# psas_c3.net
KiCad netlist of a schematic drawn in EAGLE
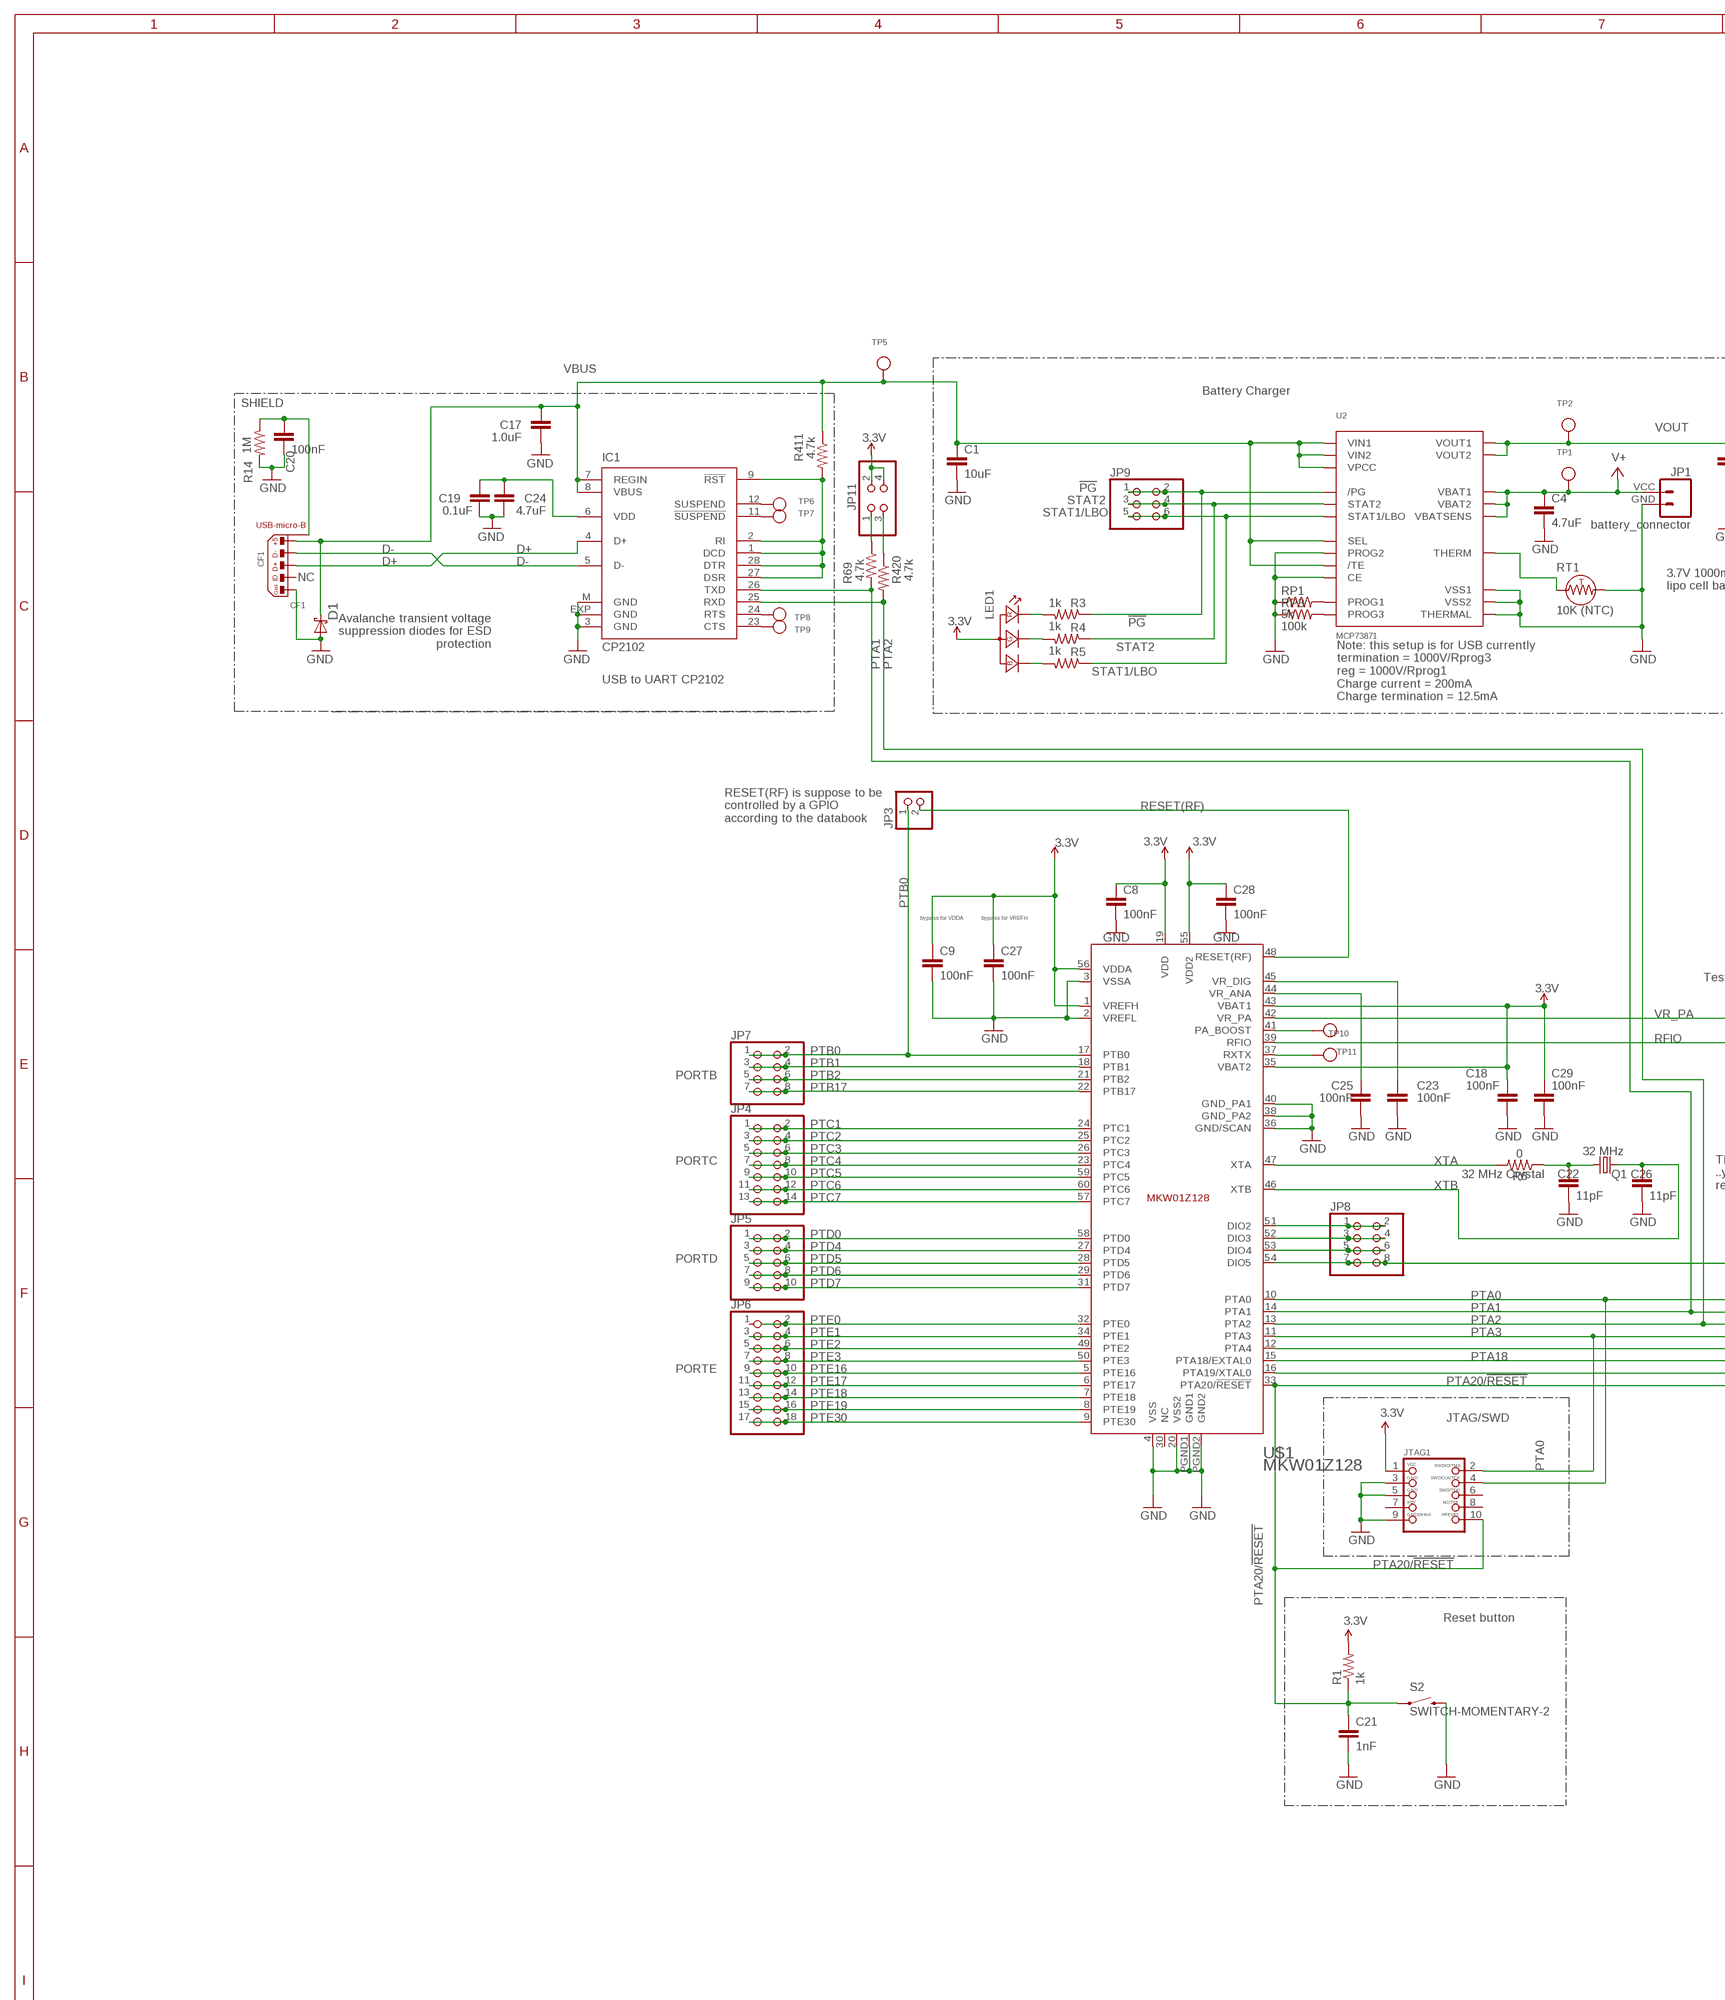
[diagram p0: schematic, sheet 1, part 1 of 2]
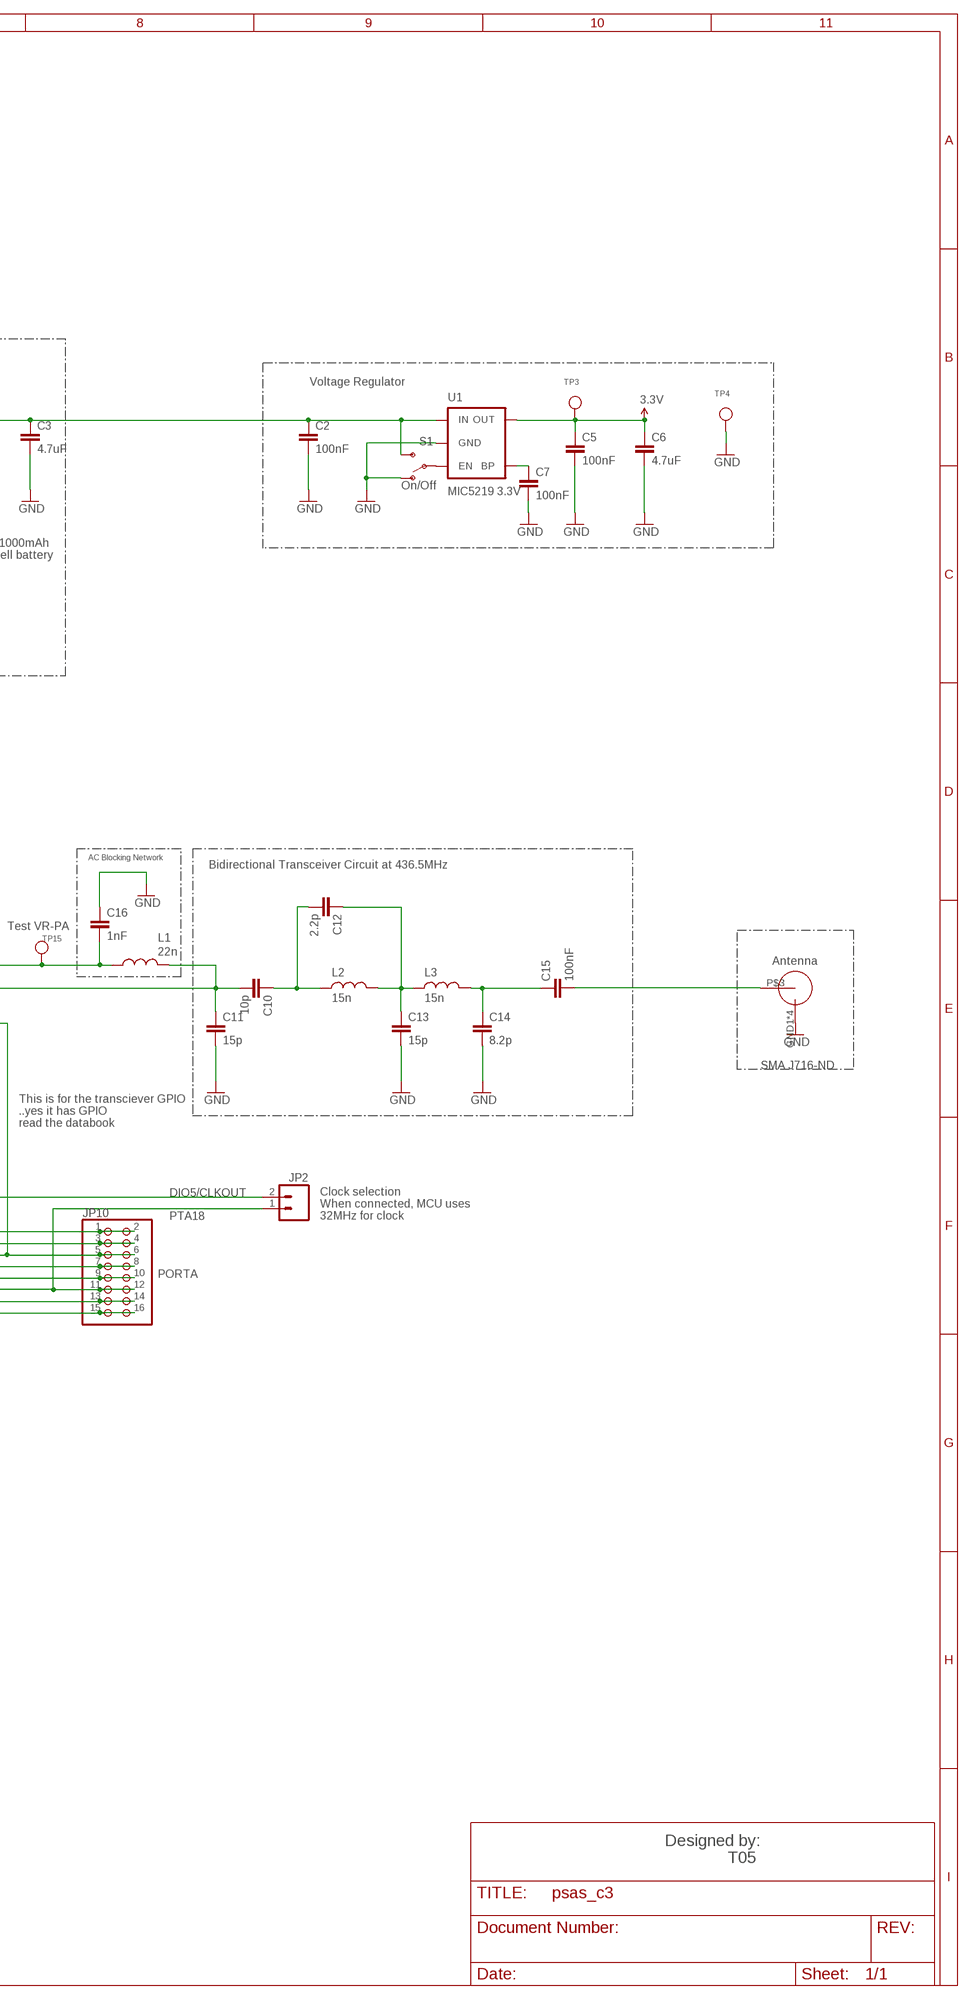
[diagram p1: schematic, sheet 1, part 2 of 2]

(export (version "E")
  (design (tool "Eeschema 10.0.6"))
  (components
    (comp (ref "C1")
      (value "10uF")
      (footprint "eagle-import:.0603-B-NOSILK")
      (libsource (lib "eagle-import") (part "rcl_custom_C-EU0603-B-NOSILK"))
    )
    (comp (ref "C2")
      (value "100nF")
      (footprint "eagle-import:.0603-B-NOSILK")
      (libsource (lib "eagle-import") (part "rcl_custom_C-EU0603-B-NOSILK"))
    )
    (comp (ref "C3")
      (value "4.7uF")
      (footprint "eagle-import:.0603-B-NOSILK")
      (libsource (lib "eagle-import") (part "rcl_custom_C-EU0603-B-NOSILK"))
    )
    (comp (ref "C4")
      (value "4.7uF")
      (footprint "eagle-import:.0603-B-NOSILK")
      (libsource (lib "eagle-import") (part "rcl_custom_C-EU0603-B-NOSILK"))
    )
    (comp (ref "C5")
      (value "100nF")
      (footprint "eagle-import:.0603-B-NOSILK")
      (libsource (lib "eagle-import") (part "rcl_custom_C-EU0603-B-NOSILK"))
    )
    (comp (ref "C6")
      (value "4.7uF")
      (footprint "eagle-import:.0603-B-NOSILK")
      (libsource (lib "eagle-import") (part "rcl_custom_C-EU0603-B-NOSILK"))
    )
    (comp (ref "C7")
      (value "100nF")
      (footprint "eagle-import:.0603-B-NOSILK")
      (libsource (lib "eagle-import") (part "rcl_custom_C-EU0603-B-NOSILK"))
    )
    (comp (ref "C8")
      (value "100nF")
      (footprint "eagle-import:.0603-B-NOSILK")
      (fields
        (field (name "MFG") "Murata Electronics North America")
        (field (name "MPN") "GRM188R71C104KA01D")
      )
      (libsource (lib "eagle-import") (part "C-EU0603-B-NOSILK"))
    )
    (comp (ref "C9")
      (value "100nF")
      (footprint "eagle-import:.0603-B-NOSILK")
      (fields
        (field (name "MFG") "Murata Electronics North America")
        (field (name "MPN") "GRM188R71C104KA01D")
      )
      (libsource (lib "eagle-import") (part "C-EU0603-B-NOSILK"))
    )
    (comp (ref "C10")
      (value "10p")
      (footprint "eagle-import:.0603-B-NOSILK")
      (libsource (lib "eagle-import") (part "rcl_custom_C-EU0603-B-NOSILK"))
    )
    (comp (ref "C11")
      (value "15p")
      (footprint "eagle-import:.0603-B-NOSILK")
      (libsource (lib "eagle-import") (part "rcl_custom_C-EU0603-B-NOSILK"))
    )
    (comp (ref "C12")
      (value "2.2p")
      (footprint "eagle-import:.0603-B-NOSILK")
      (libsource (lib "eagle-import") (part "rcl_custom_C-EU0603-B-NOSILK"))
    )
    (comp (ref "C13")
      (value "15p")
      (footprint "eagle-import:.0603-B-NOSILK")
      (libsource (lib "eagle-import") (part "rcl_custom_C-EU0603-B-NOSILK"))
    )
    (comp (ref "C14")
      (value "8.2p")
      (footprint "eagle-import:.0603-B-NOSILK")
      (libsource (lib "eagle-import") (part "rcl_custom_C-EU0603-B-NOSILK"))
    )
    (comp (ref "C15")
      (value "100nF")
      (footprint "eagle-import:.0603-B-NOSILK")
      (libsource (lib "eagle-import") (part "rcl_custom_C-EU0603-B-NOSILK"))
    )
    (comp (ref "C16")
      (value "1nF")
      (footprint "eagle-import:.0603-B-NOSILK")
      (libsource (lib "eagle-import") (part "rcl_custom_C-EU0603-B-NOSILK"))
    )
    (comp (ref "C17")
      (value "1.0uF")
      (footprint "eagle-import:.0603-B-NOSILK")
      (libsource (lib "eagle-import") (part "rcl_custom_C-EU0603-B-NOSILK"))
    )
    (comp (ref "C18")
      (value "100nF")
      (footprint "eagle-import:.0603-B-NOSILK")
      (fields
        (field (name "MFG") "Murata Electronics North America")
        (field (name "MPN") "GRM188R71C104KA01D")
      )
      (libsource (lib "eagle-import") (part "C-EU0603-B-NOSILK"))
    )
    (comp (ref "C19")
      (value "0.1uF")
      (footprint "eagle-import:.0603-B-NOSILK")
      (libsource (lib "eagle-import") (part "rcl_custom_C-EU0603-B-NOSILK"))
    )
    (comp (ref "C20")
      (value "100nF")
      (footprint "eagle-import:.0603-B-NOSILK")
      (libsource (lib "eagle-import") (part "rcl_custom_C-EU0603-B-NOSILK"))
    )
    (comp (ref "C21")
      (value "1nF")
      (footprint "eagle-import:.0603-B-NOSILK")
      (libsource (lib "eagle-import") (part "rcl_custom_C-EU0603-B-NOSILK"))
    )
    (comp (ref "C22")
      (value "11pF")
      (footprint "eagle-import:.0603-B-NOSILK")
      (fields
        (field (name "MFG") "Murata Electronics North America")
        (field (name "MPN") "GRM188R71C104KA01D")
      )
      (libsource (lib "eagle-import") (part "C-EU0603-B-NOSILK"))
    )
    (comp (ref "C23")
      (value "100nF")
      (footprint "eagle-import:.0603-B-NOSILK")
      (fields
        (field (name "MFG") "Murata Electronics North America")
        (field (name "MPN") "GRM188R71C104KA01D")
      )
      (libsource (lib "eagle-import") (part "C-EU0603-B-NOSILK"))
    )
    (comp (ref "C24")
      (value "4.7uF")
      (footprint "eagle-import:.0603-B-NOSILK")
      (libsource (lib "eagle-import") (part "rcl_custom_C-EU0603-B-NOSILK"))
    )
    (comp (ref "C25")
      (value "100nF")
      (footprint "eagle-import:.0603-B-NOSILK")
      (fields
        (field (name "MFG") "Murata Electronics North America")
        (field (name "MPN") "GRM188R71C104KA01D")
      )
      (libsource (lib "eagle-import") (part "C-EU0603-B-NOSILK"))
    )
    (comp (ref "C26")
      (value "11pF")
      (footprint "eagle-import:.0603-B-NOSILK")
      (fields
        (field (name "MFG") "Murata Electronics North America")
        (field (name "MPN") "GRM188R71C104KA01D")
      )
      (libsource (lib "eagle-import") (part "C-EU0603-B-NOSILK"))
    )
    (comp (ref "C27")
      (value "100nF")
      (footprint "eagle-import:.0603-B-NOSILK")
      (fields
        (field (name "MFG") "Murata Electronics North America")
        (field (name "MPN") "GRM188R71C104KA01D")
      )
      (libsource (lib "eagle-import") (part "C-EU0603-B-NOSILK"))
    )
    (comp (ref "C28")
      (value "100nF")
      (footprint "eagle-import:.0603-B-NOSILK")
      (fields
        (field (name "MFG") "Murata Electronics North America")
        (field (name "MPN") "GRM188R71C104KA01D")
      )
      (libsource (lib "eagle-import") (part "C-EU0603-B-NOSILK"))
    )
    (comp (ref "C29")
      (value "100nF")
      (footprint "eagle-import:.0603-B-NOSILK")
      (fields
        (field (name "MFG") "Murata Electronics North America")
        (field (name "MPN") "GRM188R71C104KA01D")
      )
      (libsource (lib "eagle-import") (part "C-EU0603-B-NOSILK"))
    )
    (comp (ref "CF1")
      (value "CF1")
      (footprint "eagle-import:USB-MICRO-B-PTH-HIROSE")
      (libsource (lib "eagle-import") (part "CON_USB-MICRO-B-RECEPTACLE-PTH-HIROSE-ZX62D-B-5P8"))
    )
    (comp (ref "D1")
      (value "DIODE_SCHOTTKY_1N5819")
      (footprint "eagle-import:SOD-123")
      (libsource (lib "eagle-import") (part "DIODE_SCHOTTKY_1N5819"))
    )
    (comp (ref "IC1")
      (value "CP2102")
      (footprint "eagle-import:MLP28")
      (fields (field (name "MF") "FARNELL") (field (name "MPN") "CP2102-GM"))
      (libsource (lib "eagle-import") (part "CP2102"))
    )
    (comp (ref "JP1")
      (value "battery_connector")
      (footprint "eagle-import:SPARKFUN-CONNECTORS_JST-2-SMD-VERT")
      (libsource (lib "eagle-import") (part "SPARKFUN-CONNECTORS_M024UCON-15767"))
    )
    (comp (ref "JP2")
      (value "M02PTH")
      (footprint "eagle-import:1X02")
      (libsource (lib "eagle-import") (part "M02PTH"))
    )
    (comp (ref "JP3")
      (value "PINHD-1X2")
      (footprint "eagle-import:1X02")
      (libsource (lib "eagle-import") (part "PINHD-1X2"))
    )
    (comp (ref "JP4")
      (value "PINHD-2X7")
      (footprint "eagle-import:2X07")
      (libsource (lib "eagle-import") (part "PINHD-2X7"))
    )
    (comp (ref "JP5")
      (value "PINHD-2X5")
      (footprint "eagle-import:2X05")
      (libsource (lib "eagle-import") (part "PINHD-2X5"))
    )
    (comp (ref "JP6")
      (value "PINHD-2X9")
      (footprint "eagle-import:2X09")
      (libsource (lib "eagle-import") (part "PINHD-2X9"))
    )
    (comp (ref "JP7")
      (value "PINHD-2X4")
      (footprint "eagle-import:2X04")
      (libsource (lib "eagle-import") (part "PINHD-2X4"))
    )
    (comp (ref "JP8")
      (value "PINHD-2X4")
      (footprint "eagle-import:2X04")
      (libsource (lib "eagle-import") (part "PINHD-2X4"))
    )
    (comp (ref "JP9")
      (value "PINHD-2X3")
      (footprint "eagle-import:2X03")
      (libsource (lib "eagle-import") (part "PINHD-2X3"))
    )
    (comp (ref "JP10")
      (value "PINHD-2X8")
      (footprint "eagle-import:2X08")
      (libsource (lib "eagle-import") (part "PINHD-2X8"))
    )
    (comp (ref "JP11")
      (value "PINHD-2X2")
      (footprint "eagle-import:2X02")
      (libsource (lib "eagle-import") (part "PINHD-2X2"))
    )
    (comp (ref "JTAG1")
      (value "JTAG-CORTEXM3MOLEX")
      (footprint "eagle-import:CORTEXM3_SWD10_MOLEX")
      (libsource (lib "eagle-import") (part "JTAG-CORTEXM3MOLEX"))
    )
    (comp (ref "L1")
      (value "22n")
      (footprint "eagle-import:.0603-B-NOSILK")
      (libsource (lib "eagle-import") (part "L-US0603-B-NOSILK"))
    )
    (comp (ref "L2")
      (value "15n")
      (footprint "eagle-import:.0603-B-NOSILK")
      (libsource (lib "eagle-import") (part "L-US0603-B-NOSILK"))
    )
    (comp (ref "L3")
      (value "15n")
      (footprint "eagle-import:.0603-B-NOSILK")
      (libsource (lib "eagle-import") (part "L-US0603-B-NOSILK"))
    )
    (comp (ref "LED1")
      (value "LED_RGB_COMMON_ANODE-1.6X1.26")
      (footprint "eagle-import:KINGBRITE_RGBLED_1.6X1.26")
      (libsource (lib "eagle-import") (part "LED_RGB_COMMON_ANODE-1.6X1.26"))
    )
    (comp (ref "Q1")
      (value "32 MHz")
      (footprint "eagle-import:FC-12M")
      (libsource (lib "eagle-import") (part "FC-12M"))
    )
    (comp (ref "R1")
      (value "1k")
      (footprint "eagle-import:.0603-B-NOSILK")
      (libsource (lib "eagle-import") (part "R-US_0603-B-NOSILK"))
    )
    (comp (ref "R3")
      (value "1k")
      (footprint "eagle-import:.0603-B-NOSILK")
      (libsource (lib "eagle-import") (part "R-US_0603-B-NOSILK"))
    )
    (comp (ref "R4")
      (value "1k")
      (footprint "eagle-import:.0603-B-NOSILK")
      (libsource (lib "eagle-import") (part "R-US_0603-B-NOSILK"))
    )
    (comp (ref "R5")
      (value "1k")
      (footprint "eagle-import:.0603-B-NOSILK")
      (libsource (lib "eagle-import") (part "R-US_0603-B-NOSILK"))
    )
    (comp (ref "R6")
      (value "0")
      (footprint "eagle-import:.0603-B-NOSILK")
      (libsource (lib "eagle-import") (part "R-US_0603-B-NOSILK"))
    )
    (comp (ref "R14")
      (value "1M")
      (footprint "eagle-import:.0603-B-NOSILK")
      (libsource (lib "eagle-import") (part "R-US_0603-B-NOSILK"))
    )
    (comp (ref "R69")
      (value "4.7k")
      (footprint "eagle-import:.0603-B-NOSILK")
      (libsource (lib "eagle-import") (part "R-US_0603-B-NOSILK"))
    )
    (comp (ref "R411")
      (value "4.7k")
      (footprint "eagle-import:.0603-B-NOSILK")
      (libsource (lib "eagle-import") (part "R-US_0603-B-NOSILK"))
    )
    (comp (ref "R420")
      (value "4.7k")
      (footprint "eagle-import:.0603-B-NOSILK")
      (libsource (lib "eagle-import") (part "R-US_0603-B-NOSILK"))
    )
    (comp (ref "RP1")
      (value "5k")
      (footprint "eagle-import:.0603-B-NOSILK")
      (libsource (lib "eagle-import") (part "R-US_0603-B-NOSILK"))
    )
    (comp (ref "RP3")
      (value "100k")
      (footprint "eagle-import:.0603-B-NOSILK")
      (libsource (lib "eagle-import") (part "R-US_0603-B-NOSILK"))
    )
    (comp (ref "RT1")
      (value "10K (NTC)")
      (footprint "eagle-import:R1206")
      (libsource (lib "eagle-import") (part "THERMISTOR-_1206"))
    )
    (comp (ref "S1")
      (value "SWITCH-SPSTPTH")
      (footprint "eagle-import:SWITCH-SPDT")
      (libsource (lib "eagle-import") (part "SWITCH-SPSTPTH"))
    )
    (comp (ref "S2")
      (value "SWITCH-MOMENTARY-2")
      (footprint "eagle-import:TACTILE_SWITCH_TALL")
      (libsource (lib "eagle-import") (part "SWITCH-MOMENTARY-2"))
    )
    (comp (ref "TP1")
      (value "TESTPOINTROUND0.5MM")
      (footprint "eagle-import:TESTPOINT_ROUND_0.5MM")
      (libsource (lib "eagle-import") (part "TESTPOINTROUND0.5MM"))
    )
    (comp (ref "TP2")
      (value "TESTPOINTROUND0.5MM")
      (footprint "eagle-import:TESTPOINT_ROUND_0.5MM")
      (libsource (lib "eagle-import") (part "TESTPOINTROUND0.5MM"))
    )
    (comp (ref "TP3")
      (value "TESTPOINTROUND0.5MM")
      (footprint "eagle-import:TESTPOINT_ROUND_0.5MM")
      (libsource (lib "eagle-import") (part "TESTPOINTROUND0.5MM"))
    )
    (comp (ref "TP4")
      (value "TESTPOINTROUND0.5MM")
      (footprint "eagle-import:TESTPOINT_ROUND_0.5MM")
      (libsource (lib "eagle-import") (part "TESTPOINTROUND0.5MM"))
    )
    (comp (ref "TP5")
      (value "TESTPOINTROUND0.5MM")
      (footprint "eagle-import:TESTPOINT_ROUND_0.5MM")
      (libsource (lib "eagle-import") (part "TESTPOINTROUND0.5MM"))
    )
    (comp (ref "TP6")
      (value "TESTPOINTROUND0.5MM")
      (footprint "eagle-import:TESTPOINT_ROUND_0.5MM")
      (libsource (lib "eagle-import") (part "TESTPOINTROUND0.5MM"))
    )
    (comp (ref "TP7")
      (value "TESTPOINTROUND0.5MM")
      (footprint "eagle-import:TESTPOINT_ROUND_0.5MM")
      (libsource (lib "eagle-import") (part "TESTPOINTROUND0.5MM"))
    )
    (comp (ref "TP8")
      (value "TESTPOINTROUND0.5MM")
      (footprint "eagle-import:TESTPOINT_ROUND_0.5MM")
      (libsource (lib "eagle-import") (part "TESTPOINTROUND0.5MM"))
    )
    (comp (ref "TP9")
      (value "TESTPOINTROUND0.5MM")
      (footprint "eagle-import:TESTPOINT_ROUND_0.5MM")
      (libsource (lib "eagle-import") (part "TESTPOINTROUND0.5MM"))
    )
    (comp (ref "TP10")
      (value "TESTPOINTROUND0.5MM")
      (footprint "eagle-import:TESTPOINT_ROUND_0.5MM")
      (libsource (lib "eagle-import") (part "TESTPOINTROUND0.5MM"))
    )
    (comp (ref "TP11")
      (value "TESTPOINTROUND0.5MM")
      (footprint "eagle-import:TESTPOINT_ROUND_0.5MM")
      (libsource (lib "eagle-import") (part "TESTPOINTROUND0.5MM"))
    )
    (comp (ref "TP15")
      (value "TESTPOINTROUND0.5MM")
      (footprint "eagle-import:TESTPOINT_ROUND_0.5MM")
      (libsource (lib "eagle-import") (part "TESTPOINTROUND0.5MM"))
    )
    (comp (ref "U$1")
      (value "MKW01Z128")
      (footprint "eagle-import:MKW01Z128")
      (fields (field (name "MPN") "MKW01Z128CHN"))
      (libsource (lib "eagle-import") (part "MKW01Z128"))
    )
    (comp (ref "U$2")
      (value "SMAJ716-ND")
      (footprint "eagle-import:SMAJ716-ND")
      (libsource (lib "eagle-import") (part "SMAJ716-ND"))
    )
    (comp (ref "U1")
      (value "MIC5219 3.3V")
      (footprint "eagle-import:SPARKFUN-POWERIC_SOT23-5")
      (libsource (lib "eagle-import") (part "SPARKFUN-POWERIC_V_REG_MIC52193.3V"))
    )
    (comp (ref "U2")
      (value "MCP73871")
      (footprint "eagle-import:QFN20_4MM")
      (libsource (lib "eagle-import") (part "MCP73871"))
    )
  )
  (nets
    (net (code "1") (name "/D+") (class "Default")
      (node (ref "CF1") (pin "3") (pinfunction "3_3") (pintype "passive"))
      (node (ref "IC1") (pin "4") (pinfunction "D+_4") (pintype "bidirectional"))
    )
    (net (code "2") (name "/D-") (class "Default")
      (node (ref "CF1") (pin "2") (pinfunction "2_2") (pintype "passive"))
      (node (ref "IC1") (pin "5") (pinfunction "D-_5") (pintype "bidirectional"))
    )
    (net (code "3") (name "/DIO5{slash}CLKOUT") (class "Default")
      (node (ref "JP2") (pin "2") (pinfunction "2_2") (pintype "passive"))
      (node (ref "JP8") (pin "7") (pinfunction "7_7") (pintype "passive"))
      (node (ref "JP8") (pin "8") (pinfunction "8_8") (pintype "passive"))
      (node (ref "U$1") (pin "54") (pinfunction "DIO5_54") (pintype "bidirectional"))
    )
    (net (code "4") (name "/PTA0") (class "Default")
      (node (ref "JP10") (pin "1") (pinfunction "1_1") (pintype "passive"))
      (node (ref "JP10") (pin "2") (pinfunction "2_2") (pintype "passive"))
      (node (ref "JTAG1") (pin "4") (pinfunction "4_4") (pintype "passive"))
      (node (ref "U$1") (pin "10") (pinfunction "PTA0_10") (pintype "bidirectional"))
    )
    (net (code "5") (name "/PTA1") (class "Default")
      (node (ref "IC1") (pin "26") (pinfunction "TXD_26") (pintype "output"))
      (node (ref "JP10") (pin "3") (pinfunction "3_3") (pintype "passive"))
      (node (ref "JP10") (pin "4") (pinfunction "4_4") (pintype "passive"))
      (node (ref "R69") (pin "2") (pinfunction "2_2") (pintype "passive"))
      (node (ref "U$1") (pin "14") (pinfunction "PTA1_14") (pintype "bidirectional"))
    )
    (net (code "6") (name "/PTA2") (class "Default")
      (node (ref "IC1") (pin "25") (pinfunction "RXD_25") (pintype "input"))
      (node (ref "JP10") (pin "5") (pinfunction "5_5") (pintype "passive"))
      (node (ref "JP10") (pin "6") (pinfunction "6_6") (pintype "passive"))
      (node (ref "R420") (pin "2") (pinfunction "2_2") (pintype "passive"))
      (node (ref "U$1") (pin "13") (pinfunction "PTA2_13") (pintype "bidirectional"))
    )
    (net (code "7") (name "/PTA3") (class "Default")
      (node (ref "JP10") (pin "7") (pinfunction "7_7") (pintype "passive"))
      (node (ref "JP10") (pin "8") (pinfunction "8_8") (pintype "passive"))
      (node (ref "JTAG1") (pin "2") (pinfunction "2_2") (pintype "passive"))
      (node (ref "U$1") (pin "11") (pinfunction "PTA3_11") (pintype "bidirectional"))
    )
    (net (code "8") (name "/PTA18") (class "Default")
      (node (ref "JP10") (pin "11") (pinfunction "11_11") (pintype "passive"))
      (node (ref "JP10") (pin "12") (pinfunction "12_12") (pintype "passive"))
      (node (ref "JP2") (pin "1") (pinfunction "1_1") (pintype "passive"))
      (node (ref "U$1") (pin "15") (pinfunction "PTA18/EXTAL0_15") (pintype "bidirectional"))
    )
    (net (code "9") (name "/PTA20{slash}~{RESET}") (class "Default")
      (node (ref "C21") (pin "1") (pinfunction "1_1") (pintype "passive"))
      (node (ref "JP10") (pin "15") (pinfunction "15_15") (pintype "passive"))
      (node (ref "JP10") (pin "16") (pinfunction "16_16") (pintype "passive"))
      (node (ref "JTAG1") (pin "10") (pinfunction "10_10") (pintype "passive"))
      (node (ref "R1") (pin "1") (pinfunction "1_1") (pintype "passive"))
      (node (ref "S2") (pin "A2") (pinfunction "1_A2") (pintype "passive"))
      (node (ref "U$1") (pin "33") (pinfunction "PTA20/~{RESET}_33") (pintype "bidirectional"))
    )
    (net (code "10") (name "/PTB0") (class "Default")
      (node (ref "JP3") (pin "1") (pinfunction "1_1") (pintype "passive"))
      (node (ref "JP7") (pin "1") (pinfunction "1_1") (pintype "passive"))
      (node (ref "JP7") (pin "2") (pinfunction "2_2") (pintype "passive"))
      (node (ref "U$1") (pin "17") (pinfunction "PTB0_17") (pintype "bidirectional"))
    )
    (net (code "11") (name "/PTB1") (class "Default")
      (node (ref "JP7") (pin "3") (pinfunction "3_3") (pintype "passive"))
      (node (ref "JP7") (pin "4") (pinfunction "4_4") (pintype "passive"))
      (node (ref "U$1") (pin "18") (pinfunction "PTB1_18") (pintype "bidirectional"))
    )
    (net (code "12") (name "/PTB2") (class "Default")
      (node (ref "JP7") (pin "5") (pinfunction "5_5") (pintype "passive"))
      (node (ref "JP7") (pin "6") (pinfunction "6_6") (pintype "passive"))
      (node (ref "U$1") (pin "21") (pinfunction "PTB2_21") (pintype "bidirectional"))
    )
    (net (code "13") (name "/PTB17") (class "Default")
      (node (ref "JP7") (pin "7") (pinfunction "7_7") (pintype "passive"))
      (node (ref "JP7") (pin "8") (pinfunction "8_8") (pintype "passive"))
      (node (ref "U$1") (pin "22") (pinfunction "PTB17_22") (pintype "bidirectional"))
    )
    (net (code "14") (name "/PTC1") (class "Default")
      (node (ref "JP4") (pin "1") (pinfunction "1_1") (pintype "passive"))
      (node (ref "JP4") (pin "2") (pinfunction "2_2") (pintype "passive"))
      (node (ref "U$1") (pin "24") (pinfunction "PTC1_24") (pintype "bidirectional"))
    )
    (net (code "15") (name "/PTC2") (class "Default")
      (node (ref "JP4") (pin "3") (pinfunction "3_3") (pintype "passive"))
      (node (ref "JP4") (pin "4") (pinfunction "4_4") (pintype "passive"))
      (node (ref "U$1") (pin "25") (pinfunction "PTC2_25") (pintype "bidirectional"))
    )
    (net (code "16") (name "/PTC3") (class "Default")
      (node (ref "JP4") (pin "5") (pinfunction "5_5") (pintype "passive"))
      (node (ref "JP4") (pin "6") (pinfunction "6_6") (pintype "passive"))
      (node (ref "U$1") (pin "26") (pinfunction "PTC3_26") (pintype "bidirectional"))
    )
    (net (code "17") (name "/PTC4") (class "Default")
      (node (ref "JP4") (pin "7") (pinfunction "7_7") (pintype "passive"))
      (node (ref "JP4") (pin "8") (pinfunction "8_8") (pintype "passive"))
      (node (ref "U$1") (pin "23") (pinfunction "PTC4_23") (pintype "bidirectional"))
    )
    (net (code "18") (name "/PTC5") (class "Default")
      (node (ref "JP4") (pin "10") (pinfunction "10_10") (pintype "passive"))
      (node (ref "JP4") (pin "9") (pinfunction "9_9") (pintype "passive"))
      (node (ref "U$1") (pin "59") (pinfunction "PTC5_59") (pintype "bidirectional"))
    )
    (net (code "19") (name "/PTC6") (class "Default")
      (node (ref "JP4") (pin "11") (pinfunction "11_11") (pintype "passive"))
      (node (ref "JP4") (pin "12") (pinfunction "12_12") (pintype "passive"))
      (node (ref "U$1") (pin "60") (pinfunction "PTC6_60") (pintype "bidirectional"))
    )
    (net (code "20") (name "/PTC7") (class "Default")
      (node (ref "JP4") (pin "13") (pinfunction "13_13") (pintype "passive"))
      (node (ref "JP4") (pin "14") (pinfunction "14_14") (pintype "passive"))
      (node (ref "U$1") (pin "57") (pinfunction "PTC7_57") (pintype "bidirectional"))
    )
    (net (code "21") (name "/PTD0") (class "Default")
      (node (ref "JP5") (pin "1") (pinfunction "1_1") (pintype "passive"))
      (node (ref "JP5") (pin "2") (pinfunction "2_2") (pintype "passive"))
      (node (ref "U$1") (pin "58") (pinfunction "PTD0_58") (pintype "bidirectional"))
    )
    (net (code "22") (name "/PTD4") (class "Default")
      (node (ref "JP5") (pin "3") (pinfunction "3_3") (pintype "passive"))
      (node (ref "JP5") (pin "4") (pinfunction "4_4") (pintype "passive"))
      (node (ref "U$1") (pin "27") (pinfunction "PTD4_27") (pintype "bidirectional"))
    )
    (net (code "23") (name "/PTD5") (class "Default")
      (node (ref "JP5") (pin "5") (pinfunction "5_5") (pintype "passive"))
      (node (ref "JP5") (pin "6") (pinfunction "6_6") (pintype "passive"))
      (node (ref "U$1") (pin "28") (pinfunction "PTD5_28") (pintype "bidirectional"))
    )
    (net (code "24") (name "/PTD6") (class "Default")
      (node (ref "JP5") (pin "7") (pinfunction "7_7") (pintype "passive"))
      (node (ref "JP5") (pin "8") (pinfunction "8_8") (pintype "passive"))
      (node (ref "U$1") (pin "29") (pinfunction "PTD6_29") (pintype "bidirectional"))
    )
    (net (code "25") (name "/PTD7") (class "Default")
      (node (ref "JP5") (pin "10") (pinfunction "10_10") (pintype "passive"))
      (node (ref "JP5") (pin "9") (pinfunction "9_9") (pintype "passive"))
      (node (ref "U$1") (pin "31") (pinfunction "PTD7_31") (pintype "bidirectional"))
    )
    (net (code "26") (name "/PTE0") (class "Default")
      (node (ref "JP6") (pin "2") (pinfunction "2_2") (pintype "passive"))
      (node (ref "U$1") (pin "32") (pinfunction "PTE0_32") (pintype "bidirectional"))
    )
    (net (code "27") (name "/PTE1") (class "Default")
      (node (ref "JP6") (pin "3") (pinfunction "3_3") (pintype "passive"))
      (node (ref "JP6") (pin "4") (pinfunction "4_4") (pintype "passive"))
      (node (ref "U$1") (pin "34") (pinfunction "PTE1_34") (pintype "bidirectional"))
    )
    (net (code "28") (name "/PTE2") (class "Default")
      (node (ref "JP6") (pin "5") (pinfunction "5_5") (pintype "passive"))
      (node (ref "JP6") (pin "6") (pinfunction "6_6") (pintype "passive"))
      (node (ref "U$1") (pin "49") (pinfunction "PTE2_49") (pintype "bidirectional"))
    )
    (net (code "29") (name "/PTE3") (class "Default")
      (node (ref "JP6") (pin "7") (pinfunction "7_7") (pintype "passive"))
      (node (ref "JP6") (pin "8") (pinfunction "8_8") (pintype "passive"))
      (node (ref "U$1") (pin "50") (pinfunction "PTE3_50") (pintype "bidirectional"))
    )
    (net (code "30") (name "/PTE16") (class "Default")
      (node (ref "JP6") (pin "10") (pinfunction "10_10") (pintype "passive"))
      (node (ref "JP6") (pin "9") (pinfunction "9_9") (pintype "passive"))
      (node (ref "U$1") (pin "5") (pinfunction "PTE16_5") (pintype "bidirectional"))
    )
    (net (code "31") (name "/PTE17") (class "Default")
      (node (ref "JP6") (pin "11") (pinfunction "11_11") (pintype "passive"))
      (node (ref "JP6") (pin "12") (pinfunction "12_12") (pintype "passive"))
      (node (ref "U$1") (pin "6") (pinfunction "PTE17_6") (pintype "bidirectional"))
    )
    (net (code "32") (name "/PTE18") (class "Default")
      (node (ref "JP6") (pin "13") (pinfunction "13_13") (pintype "passive"))
      (node (ref "JP6") (pin "14") (pinfunction "14_14") (pintype "passive"))
      (node (ref "U$1") (pin "7") (pinfunction "PTE18_7") (pintype "bidirectional"))
    )
    (net (code "33") (name "/PTE19") (class "Default")
      (node (ref "JP6") (pin "15") (pinfunction "15_15") (pintype "passive"))
      (node (ref "JP6") (pin "16") (pinfunction "16_16") (pintype "passive"))
      (node (ref "U$1") (pin "8") (pinfunction "PTE19_8") (pintype "bidirectional"))
    )
    (net (code "34") (name "/PTE30") (class "Default")
      (node (ref "JP6") (pin "17") (pinfunction "17_17") (pintype "passive"))
      (node (ref "JP6") (pin "18") (pinfunction "18_18") (pintype "passive"))
      (node (ref "U$1") (pin "9") (pinfunction "PTE30_9") (pintype "bidirectional"))
    )
    (net (code "35") (name "/RESET(RF)") (class "Default")
      (node (ref "JP3") (pin "2") (pinfunction "2_2") (pintype "passive"))
      (node (ref "U$1") (pin "48") (pinfunction "RESET(RF)_48") (pintype "input"))
    )
    (net (code "36") (name "/RFIO") (class "Default")
      (node (ref "C10") (pin "2") (pinfunction "2_2") (pintype "passive"))
      (node (ref "C11") (pin "1") (pinfunction "1_1") (pintype "passive"))
      (node (ref "L1") (pin "2") (pinfunction "2_2") (pintype "passive"))
      (node (ref "U$1") (pin "39") (pinfunction "RFIO_39") (pintype "bidirectional"))
    )
    (net (code "37") (name "/STAT1{slash}LBO") (class "Default")
      (node (ref "JP9") (pin "5") (pinfunction "5_5") (pintype "passive"))
      (node (ref "JP9") (pin "6") (pinfunction "6_6") (pintype "passive"))
      (node (ref "R5") (pin "1") (pinfunction "1_1") (pintype "passive"))
      (node (ref "U2") (pin "P$8") (pinfunction "STAT1/LBO_P$8") (pintype "output"))
    )
    (net (code "38") (name "/STAT2") (class "Default")
      (node (ref "JP9") (pin "3") (pinfunction "3_3") (pintype "passive"))
      (node (ref "JP9") (pin "4") (pinfunction "4_4") (pintype "passive"))
      (node (ref "R4") (pin "1") (pinfunction "1_1") (pintype "passive"))
      (node (ref "U2") (pin "P$7") (pinfunction "STAT2_P$7") (pintype "output"))
    )
    (net (code "39") (name "/VOUT") (class "Default")
      (node (ref "C2") (pin "1") (pinfunction "1_1") (pintype "passive"))
      (node (ref "C3") (pin "1") (pinfunction "1_1") (pintype "passive"))
      (node (ref "S1") (pin "3") (pinfunction "S_3") (pintype "passive"))
      (node (ref "TP2") (pin "P$1") (pinfunction "P$1_P$1") (pintype "bidirectional"))
      (node (ref "U1") (pin "1") (pinfunction "IN_1") (pintype "input"))
      (node (ref "U2") (pin "P$1") (pinfunction "VOUT1_P$1") (pintype "power_in"))
      (node (ref "U2") (pin "P$20") (pinfunction "VOUT2_P$20") (pintype "power_in"))
    )
    (net (code "40") (name "/VR_PA") (class "Default")
      (node (ref "C16") (pin "2") (pinfunction "2_2") (pintype "passive"))
      (node (ref "L1") (pin "1") (pinfunction "1_1") (pintype "passive"))
      (node (ref "TP15") (pin "P$1") (pinfunction "P$1_P$1") (pintype "bidirectional"))
      (node (ref "U$1") (pin "42") (pinfunction "VR_PA_42") (pintype "output"))
    )
    (net (code "41") (name "/XTA") (class "Default")
      (node (ref "R6") (pin "2") (pinfunction "2_2") (pintype "passive"))
      (node (ref "U$1") (pin "47") (pinfunction "XTA_47") (pintype "passive"))
    )
    (net (code "42") (name "/XTB") (class "Default")
      (node (ref "C26") (pin "1") (pinfunction "1_1") (pintype "passive"))
      (node (ref "Q1") (pin "1") (pinfunction "1_1") (pintype "passive"))
      (node (ref "U$1") (pin "46") (pinfunction "XTB_46") (pintype "passive"))
    )
    (net (code "43") (name "/~{PG}") (class "Default")
      (node (ref "JP9") (pin "1") (pinfunction "1_1") (pintype "passive"))
      (node (ref "JP9") (pin "2") (pinfunction "2_2") (pintype "passive"))
      (node (ref "R3") (pin "1") (pinfunction "1_1") (pintype "passive"))
      (node (ref "U2") (pin "P$6") (pinfunction "/PG_P$6") (pintype "output"))
    )
    (net (code "44") (name "3.3V") (class "Default")
      (node (ref "C18") (pin "1") (pinfunction "1_1") (pintype "passive"))
      (node (ref "C27") (pin "1") (pinfunction "1_1") (pintype "passive"))
      (node (ref "C28") (pin "1") (pinfunction "1_1") (pintype "passive"))
      (node (ref "C29") (pin "1") (pinfunction "1_1") (pintype "passive"))
      (node (ref "C5") (pin "1") (pinfunction "1_1") (pintype "passive"))
      (node (ref "C6") (pin "1") (pinfunction "1_1") (pintype "passive"))
      (node (ref "C8") (pin "1") (pinfunction "1_1") (pintype "passive"))
      (node (ref "C9") (pin "1") (pinfunction "1_1") (pintype "passive"))
      (node (ref "JP11") (pin "2") (pinfunction "2_2") (pintype "passive"))
      (node (ref "JP11") (pin "4") (pinfunction "4_4") (pintype "passive"))
      (node (ref "JTAG1") (pin "1") (pinfunction "1_1") (pintype "passive"))
      (node (ref "LED1") (pin "2") (pinfunction "COMMON_ANODE_2") (pintype "passive"))
      (node (ref "R1") (pin "2") (pinfunction "2_2") (pintype "passive"))
      (node (ref "TP3") (pin "P$1") (pinfunction "P$1_P$1") (pintype "bidirectional"))
      (node (ref "U$1") (pin "1") (pinfunction "VREFH_1") (pintype "input"))
      (node (ref "U$1") (pin "19") (pinfunction "VDD_19") (pintype "power_in"))
      (node (ref "U$1") (pin "35") (pinfunction "VBAT2_35") (pintype "power_in"))
      (node (ref "U$1") (pin "43") (pinfunction "VBAT1_43") (pintype "power_in"))
      (node (ref "U$1") (pin "55") (pinfunction "VDD2_55") (pintype "power_in"))
      (node (ref "U$1") (pin "56") (pinfunction "VDDA_56") (pintype "power_in"))
      (node (ref "U1") (pin "5") (pinfunction "OUT_5") (pintype "passive"))
    )
    (net (code "45") (name "GND") (class "Default")
      (node (ref "C1") (pin "2") (pinfunction "2_2") (pintype "passive"))
      (node (ref "C11") (pin "2") (pinfunction "2_2") (pintype "passive"))
      (node (ref "C13") (pin "2") (pinfunction "2_2") (pintype "passive"))
      (node (ref "C14") (pin "2") (pinfunction "2_2") (pintype "passive"))
      (node (ref "C16") (pin "1") (pinfunction "1_1") (pintype "passive"))
      (node (ref "C17") (pin "2") (pinfunction "2_2") (pintype "passive"))
      (node (ref "C18") (pin "2") (pinfunction "2_2") (pintype "passive"))
      (node (ref "C19") (pin "2") (pinfunction "2_2") (pintype "passive"))
      (node (ref "C2") (pin "2") (pinfunction "2_2") (pintype "passive"))
      (node (ref "C20") (pin "2") (pinfunction "2_2") (pintype "passive"))
      (node (ref "C21") (pin "2") (pinfunction "2_2") (pintype "passive"))
      (node (ref "C22") (pin "2") (pinfunction "2_2") (pintype "passive"))
      (node (ref "C23") (pin "2") (pinfunction "2_2") (pintype "passive"))
      (node (ref "C24") (pin "2") (pinfunction "2_2") (pintype "passive"))
      (node (ref "C25") (pin "2") (pinfunction "2_2") (pintype "passive"))
      (node (ref "C26") (pin "2") (pinfunction "2_2") (pintype "passive"))
      (node (ref "C27") (pin "2") (pinfunction "2_2") (pintype "passive"))
      (node (ref "C28") (pin "2") (pinfunction "2_2") (pintype "passive"))
      (node (ref "C29") (pin "2") (pinfunction "2_2") (pintype "passive"))
      (node (ref "C3") (pin "2") (pinfunction "2_2") (pintype "passive"))
      (node (ref "C4") (pin "2") (pinfunction "2_2") (pintype "passive"))
      (node (ref "C5") (pin "2") (pinfunction "2_2") (pintype "passive"))
      (node (ref "C6") (pin "2") (pinfunction "2_2") (pintype "passive"))
      (node (ref "C7") (pin "2") (pinfunction "2_2") (pintype "passive"))
      (node (ref "C8") (pin "2") (pinfunction "2_2") (pintype "passive"))
      (node (ref "C9") (pin "2") (pinfunction "2_2") (pintype "passive"))
      (node (ref "CF1") (pin "5") (pinfunction "5_5") (pintype "passive"))
      (node (ref "D1") (pin "ANODE") (pinfunction "ANODE_ANODE") (pintype "passive"))
      (node (ref "IC1") (pin "3") (pinfunction "GND_3") (pintype "power_in"))
      (node (ref "IC1") (pin "EXP") (pinfunction "GND_EXP") (pintype "power_in"))
      (node (ref "IC1") (pin "M") (pinfunction "GND_M") (pintype "power_in"))
      (node (ref "JP1") (pin "GND") (pinfunction "1_GND") (pintype "passive"))
      (node (ref "JTAG1") (pin "3") (pinfunction "3_3") (pintype "passive"))
      (node (ref "JTAG1") (pin "5") (pinfunction "5_5") (pintype "passive"))
      (node (ref "JTAG1") (pin "9") (pinfunction "9_9") (pintype "passive"))
      (node (ref "R14") (pin "2") (pinfunction "2_2") (pintype "passive"))
      (node (ref "RP1") (pin "1") (pinfunction "1_1") (pintype "passive"))
      (node (ref "RP3") (pin "1") (pinfunction "1_1") (pintype "passive"))
      (node (ref "RT1") (pin "2") (pinfunction "2_2") (pintype "passive"))
      (node (ref "S1") (pin "1") (pinfunction "O_1") (pintype "passive"))
      (node (ref "S2") (pin "B2") (pinfunction "2_B2") (pintype "passive"))
      (node (ref "TP4") (pin "P$1") (pinfunction "P$1_P$1") (pintype "bidirectional"))
      (node (ref "U$1") (pin "2") (pinfunction "VREFL_2") (pintype "input"))
      (node (ref "U$1") (pin "20") (pinfunction "VSS2_20") (pintype "power_in"))
      (node (ref "U$1") (pin "3") (pinfunction "VSSA_3") (pintype "power_in"))
      (node (ref "U$1") (pin "36") (pinfunction "GND/SCAN_36") (pintype "power_in"))
      (node (ref "U$1") (pin "38") (pinfunction "GND_PA2_38") (pintype "power_in"))
      (node (ref "U$1") (pin "4") (pinfunction "VSS_4") (pintype "power_in"))
      (node (ref "U$1") (pin "40") (pinfunction "GND_PA1_40") (pintype "power_in"))
      (node (ref "U$1") (pin "PGND1") (pinfunction "GND1_PGND1") (pintype "power_in"))
      (node (ref "U$1") (pin "PGND2") (pinfunction "GND2_PGND2") (pintype "power_in"))
      (node (ref "U$2") (pin "GND1") (pinfunction "OUTERCONDUCTOR_GND1") (pintype "bidirectional"))
      (node (ref "U$2") (pin "GND2") (pinfunction "OUTERCONDUCTOR_GND2") (pintype "bidirectional"))
      (node (ref "U$2") (pin "GND3") (pinfunction "OUTERCONDUCTOR_GND3") (pintype "bidirectional"))
      (node (ref "U$2") (pin "GND4") (pinfunction "OUTERCONDUCTOR_GND4") (pintype "bidirectional"))
      (node (ref "U1") (pin "2") (pinfunction "GND_2") (pintype "input"))
      (node (ref "U2") (pin "P$10") (pinfunction "VSS1_P$10") (pintype "power_in"))
      (node (ref "U2") (pin "P$11") (pinfunction "VSS2_P$11") (pintype "power_in"))
      (node (ref "U2") (pin "P$17") (pinfunction "CE_P$17") (pintype "input"))
      (node (ref "U2") (pin "P$21") (pinfunction "THERMAL_P$21") (pintype "power_in"))
      (node (ref "U2") (pin "P$4") (pinfunction "PROG2_P$4") (pintype "input"))
    )
    (net (code "46") (name "Net-(C10-Pad1)") (class "Default")
      (node (ref "C10") (pin "1") (pinfunction "1_1") (pintype "passive"))
      (node (ref "C12") (pin "2") (pinfunction "2_2") (pintype "passive"))
      (node (ref "L2") (pin "1") (pinfunction "1_1") (pintype "passive"))
    )
    (net (code "47") (name "Net-(C12-Pad1)") (class "Default")
      (node (ref "C12") (pin "1") (pinfunction "1_1") (pintype "passive"))
      (node (ref "C13") (pin "1") (pinfunction "1_1") (pintype "passive"))
      (node (ref "L2") (pin "2") (pinfunction "2_2") (pintype "passive"))
      (node (ref "L3") (pin "1") (pinfunction "1_1") (pintype "passive"))
    )
    (net (code "48") (name "Net-(C14-Pad1)") (class "Default")
      (node (ref "C14") (pin "1") (pinfunction "1_1") (pintype "passive"))
      (node (ref "C15") (pin "1") (pinfunction "1_1") (pintype "passive"))
      (node (ref "L3") (pin "2") (pinfunction "2_2") (pintype "passive"))
    )
    (net (code "49") (name "Net-(C20-Pad1)") (class "Default")
      (node (ref "C20") (pin "1") (pinfunction "1_1") (pintype "passive"))
      (node (ref "CF1") (pin "S1") (pinfunction "SHIELD_S1") (pintype "passive"))
      (node (ref "CF1") (pin "S2") (pinfunction "SHIELD_S2") (pintype "passive"))
      (node (ref "CF1") (pin "S3") (pinfunction "SHIELD_S3") (pintype "passive"))
      (node (ref "CF1") (pin "S4") (pinfunction "SHIELD_S4") (pintype "passive"))
      (node (ref "R14") (pin "1") (pinfunction "1_1") (pintype "passive"))
    )
    (net (code "50") (name "Net-(C22-Pad1)") (class "Default")
      (node (ref "C22") (pin "1") (pinfunction "1_1") (pintype "passive"))
      (node (ref "Q1") (pin "2") (pinfunction "2_2") (pintype "passive"))
      (node (ref "R6") (pin "1") (pinfunction "1_1") (pintype "passive"))
    )
    (net (code "51") (name "Net-(IC1-CTS)") (class "Default")
      (node (ref "IC1") (pin "23") (pinfunction "CTS_23") (pintype "input"))
      (node (ref "TP9") (pin "P$1") (pinfunction "P$1_P$1") (pintype "bidirectional"))
    )
    (net (code "52") (name "Net-(IC1-DCD)") (class "Default")
      (node (ref "IC1") (pin "1") (pinfunction "DCD_1") (pintype "input"))
      (node (ref "IC1") (pin "2") (pinfunction "RI_2") (pintype "input"))
      (node (ref "IC1") (pin "27") (pinfunction "DSR_27") (pintype "input"))
      (node (ref "IC1") (pin "28") (pinfunction "DTR_28") (pintype "output"))
      (node (ref "IC1") (pin "9") (pinfunction "~{RST}_9") (pintype "bidirectional"))
      (node (ref "R411") (pin "2") (pinfunction "2_2") (pintype "passive"))
    )
    (net (code "53") (name "Net-(IC1-REGIN)") (class "Default")
      (node (ref "C1") (pin "1") (pinfunction "1_1") (pintype "passive"))
      (node (ref "C17") (pin "1") (pinfunction "1_1") (pintype "passive"))
      (node (ref "CF1") (pin "1") (pinfunction "1_1") (pintype "passive"))
      (node (ref "D1") (pin "CATHODE") (pinfunction "CATHODE_CATHODE") (pintype "passive"))
      (node (ref "IC1") (pin "7") (pinfunction "REGIN_7") (pintype "passive"))
      (node (ref "IC1") (pin "8") (pinfunction "VBUS_8") (pintype "input"))
      (node (ref "R411") (pin "1") (pinfunction "1_1") (pintype "passive"))
      (node (ref "TP5") (pin "P$1") (pinfunction "P$1_P$1") (pintype "bidirectional"))
      (node (ref "U2") (pin "P$18") (pinfunction "VIN1_P$18") (pintype "power_in"))
      (node (ref "U2") (pin "P$19") (pinfunction "VIN2_P$19") (pintype "power_in"))
      (node (ref "U2") (pin "P$2") (pinfunction "VPCC_P$2") (pintype "passive"))
      (node (ref "U2") (pin "P$3") (pinfunction "SEL_P$3") (pintype "input"))
      (node (ref "U2") (pin "P$9") (pinfunction "/TE_P$9") (pintype "input"))
    )
    (net (code "54") (name "Net-(IC1-RTS)") (class "Default")
      (node (ref "IC1") (pin "24") (pinfunction "RTS_24") (pintype "output"))
      (node (ref "TP8") (pin "P$1") (pinfunction "P$1_P$1") (pintype "bidirectional"))
    )
    (net (code "55") (name "Net-(IC1-SUSPEND)") (class "Default")
      (node (ref "IC1") (pin "12") (pinfunction "SUSPEND_12") (pintype "output"))
      (node (ref "TP6") (pin "P$1") (pinfunction "P$1_P$1") (pintype "bidirectional"))
    )
    (net (code "56") (name "Net-(IC1-VDD)") (class "Default")
      (node (ref "C19") (pin "1") (pinfunction "1_1") (pintype "passive"))
      (node (ref "C24") (pin "1") (pinfunction "1_1") (pintype "passive"))
      (node (ref "IC1") (pin "6") (pinfunction "VDD_6") (pintype "power_in"))
    )
    (net (code "57") (name "Net-(IC1-~{SUSPEND})") (class "Default")
      (node (ref "IC1") (pin "11") (pinfunction "~{SUSPEND}_11") (pintype "output"))
      (node (ref "TP7") (pin "P$1") (pinfunction "P$1_P$1") (pintype "bidirectional"))
    )
    (net (code "58") (name "Net-(JP11-Pad1)") (class "Default")
      (node (ref "JP11") (pin "1") (pinfunction "1_1") (pintype "passive"))
      (node (ref "R69") (pin "1") (pinfunction "1_1") (pintype "passive"))
    )
    (net (code "59") (name "Net-(JP11-Pad3)") (class "Default")
      (node (ref "JP11") (pin "3") (pinfunction "3_3") (pintype "passive"))
      (node (ref "R420") (pin "1") (pinfunction "1_1") (pintype "passive"))
    )
    (net (code "60") (name "Net-(LED1-BK)") (class "Default")
      (node (ref "LED1") (pin "1") (pinfunction "BK_1") (pintype "passive"))
      (node (ref "R5") (pin "2") (pinfunction "2_2") (pintype "passive"))
    )
    (net (code "61") (name "Net-(LED1-GK)") (class "Default")
      (node (ref "LED1") (pin "4") (pinfunction "GK_4") (pintype "passive"))
      (node (ref "R4") (pin "2") (pinfunction "2_2") (pintype "passive"))
    )
    (net (code "62") (name "Net-(LED1-RK)") (class "Default")
      (node (ref "LED1") (pin "3") (pinfunction "RK_3") (pintype "passive"))
      (node (ref "R3") (pin "2") (pinfunction "2_2") (pintype "passive"))
    )
    (net (code "63") (name "Net-(S1-P)") (class "Default")
      (node (ref "S1") (pin "2") (pinfunction "P_2") (pintype "passive"))
      (node (ref "U1") (pin "3") (pinfunction "EN_3") (pintype "input"))
    )
    (net (code "64") (name "Net-(U$1-DIO2)") (class "Default")
      (node (ref "JP8") (pin "1") (pinfunction "1_1") (pintype "passive"))
      (node (ref "JP8") (pin "2") (pinfunction "2_2") (pintype "passive"))
      (node (ref "U$1") (pin "51") (pinfunction "DIO2_51") (pintype "bidirectional"))
    )
    (net (code "65") (name "Net-(U$1-DIO3)") (class "Default")
      (node (ref "JP8") (pin "3") (pinfunction "3_3") (pintype "passive"))
      (node (ref "JP8") (pin "4") (pinfunction "4_4") (pintype "passive"))
      (node (ref "U$1") (pin "52") (pinfunction "DIO3_52") (pintype "bidirectional"))
    )
    (net (code "66") (name "Net-(U$1-DIO4)") (class "Default")
      (node (ref "JP8") (pin "5") (pinfunction "5_5") (pintype "passive"))
      (node (ref "JP8") (pin "6") (pinfunction "6_6") (pintype "passive"))
      (node (ref "U$1") (pin "53") (pinfunction "DIO4_53") (pintype "bidirectional"))
    )
    (net (code "67") (name "Net-(U$1-PA_BOOST)") (class "Default")
      (node (ref "TP10") (pin "P$1") (pinfunction "P$1_P$1") (pintype "bidirectional"))
      (node (ref "U$1") (pin "41") (pinfunction "PA_BOOST_41") (pintype "output"))
    )
    (net (code "68") (name "Net-(U$1-PTA4)") (class "Default")
      (node (ref "JP10") (pin "10") (pinfunction "10_10") (pintype "passive"))
      (node (ref "JP10") (pin "9") (pinfunction "9_9") (pintype "passive"))
      (node (ref "U$1") (pin "12") (pinfunction "PTA4_12") (pintype "bidirectional"))
    )
    (net (code "69") (name "Net-(U$1-PTA19{slash}XTAL0)") (class "Default")
      (node (ref "JP10") (pin "13") (pinfunction "13_13") (pintype "passive"))
      (node (ref "JP10") (pin "14") (pinfunction "14_14") (pintype "passive"))
      (node (ref "U$1") (pin "16") (pinfunction "PTA19/XTAL0_16") (pintype "bidirectional"))
    )
    (net (code "70") (name "Net-(U$1-RXTX)") (class "Default")
      (node (ref "TP11") (pin "P$1") (pinfunction "P$1_P$1") (pintype "bidirectional"))
      (node (ref "U$1") (pin "37") (pinfunction "RXTX_37") (pintype "output"))
    )
    (net (code "71") (name "Net-(U$1-VR_ANA)") (class "Default")
      (node (ref "C25") (pin "1") (pinfunction "1_1") (pintype "passive"))
      (node (ref "U$1") (pin "44") (pinfunction "VR_ANA_44") (pintype "output"))
    )
    (net (code "72") (name "Net-(U$1-VR_DIG)") (class "Default")
      (node (ref "C23") (pin "1") (pinfunction "1_1") (pintype "passive"))
      (node (ref "U$1") (pin "45") (pinfunction "VR_DIG_45") (pintype "output"))
    )
    (net (code "73") (name "Net-(U$2-CENTERCONDUCTOR)") (class "Default")
      (node (ref "C15") (pin "2") (pinfunction "2_2") (pintype "passive"))
      (node (ref "U$2") (pin "P$3") (pinfunction "CENTERCONDUCTOR_P$3") (pintype "bidirectional"))
    )
    (net (code "74") (name "Net-(U1-BP)") (class "Default")
      (node (ref "C7") (pin "1") (pinfunction "1_1") (pintype "passive"))
      (node (ref "U1") (pin "4") (pinfunction "BP_4") (pintype "input"))
    )
    (net (code "75") (name "Net-(U2-PROG1)") (class "Default")
      (node (ref "RP1") (pin "2") (pinfunction "2_2") (pintype "passive"))
      (node (ref "U2") (pin "P$13") (pinfunction "PROG1_P$13") (pintype "passive"))
    )
    (net (code "76") (name "Net-(U2-PROG3)") (class "Default")
      (node (ref "RP3") (pin "2") (pinfunction "2_2") (pintype "passive"))
      (node (ref "U2") (pin "P$12") (pinfunction "PROG3_P$12") (pintype "passive"))
    )
    (net (code "77") (name "Net-(U2-THERM)") (class "Default")
      (node (ref "RT1") (pin "1") (pinfunction "1_1") (pintype "passive"))
      (node (ref "U2") (pin "P$5") (pinfunction "THERM_P$5") (pintype "passive"))
    )
    (net (code "78") (name "V+") (class "Default")
      (node (ref "C4") (pin "1") (pinfunction "1_1") (pintype "passive"))
      (node (ref "JP1") (pin "VCC") (pinfunction "2_VCC") (pintype "passive"))
      (node (ref "TP1") (pin "P$1") (pinfunction "P$1_P$1") (pintype "bidirectional"))
      (node (ref "U2") (pin "P$14") (pinfunction "VBAT1_P$14") (pintype "power_in"))
      (node (ref "U2") (pin "P$15") (pinfunction "VBAT2_P$15") (pintype "power_in"))
      (node (ref "U2") (pin "P$16") (pinfunction "VBATSENS_P$16") (pintype "passive"))
    )
    (net (code "79") (name "unconnected-(CF1-Pad4)") (class "Default")
      (node (ref "CF1") (pin "4") (pinfunction "4_4") (pintype "passive"))
    )
    (net (code "80") (name "unconnected-(JP6-Pad1)") (class "Default")
      (node (ref "JP6") (pin "1") (pinfunction "1_1") (pintype "passive"))
    )
    (net (code "81") (name "unconnected-(JTAG1-Pad6)") (class "Default")
      (node (ref "JTAG1") (pin "6") (pinfunction "6_6") (pintype "passive"))
    )
    (net (code "82") (name "unconnected-(JTAG1-Pad7)") (class "Default")
      (node (ref "JTAG1") (pin "7") (pinfunction "7_7") (pintype "passive"))
    )
    (net (code "83") (name "unconnected-(JTAG1-Pad8)") (class "Default")
      (node (ref "JTAG1") (pin "8") (pinfunction "8_8") (pintype "passive"))
    )
    (net (code "84") (name "unconnected-(U$1-NC-Pad30)") (class "Default")
      (node (ref "U$1") (pin "30") (pinfunction "NC_30") (pintype "no_connect"))
    )
  )
)
